# PWR_MGMT.net
KiCad netlist of a schematic drawn in Altium Designer
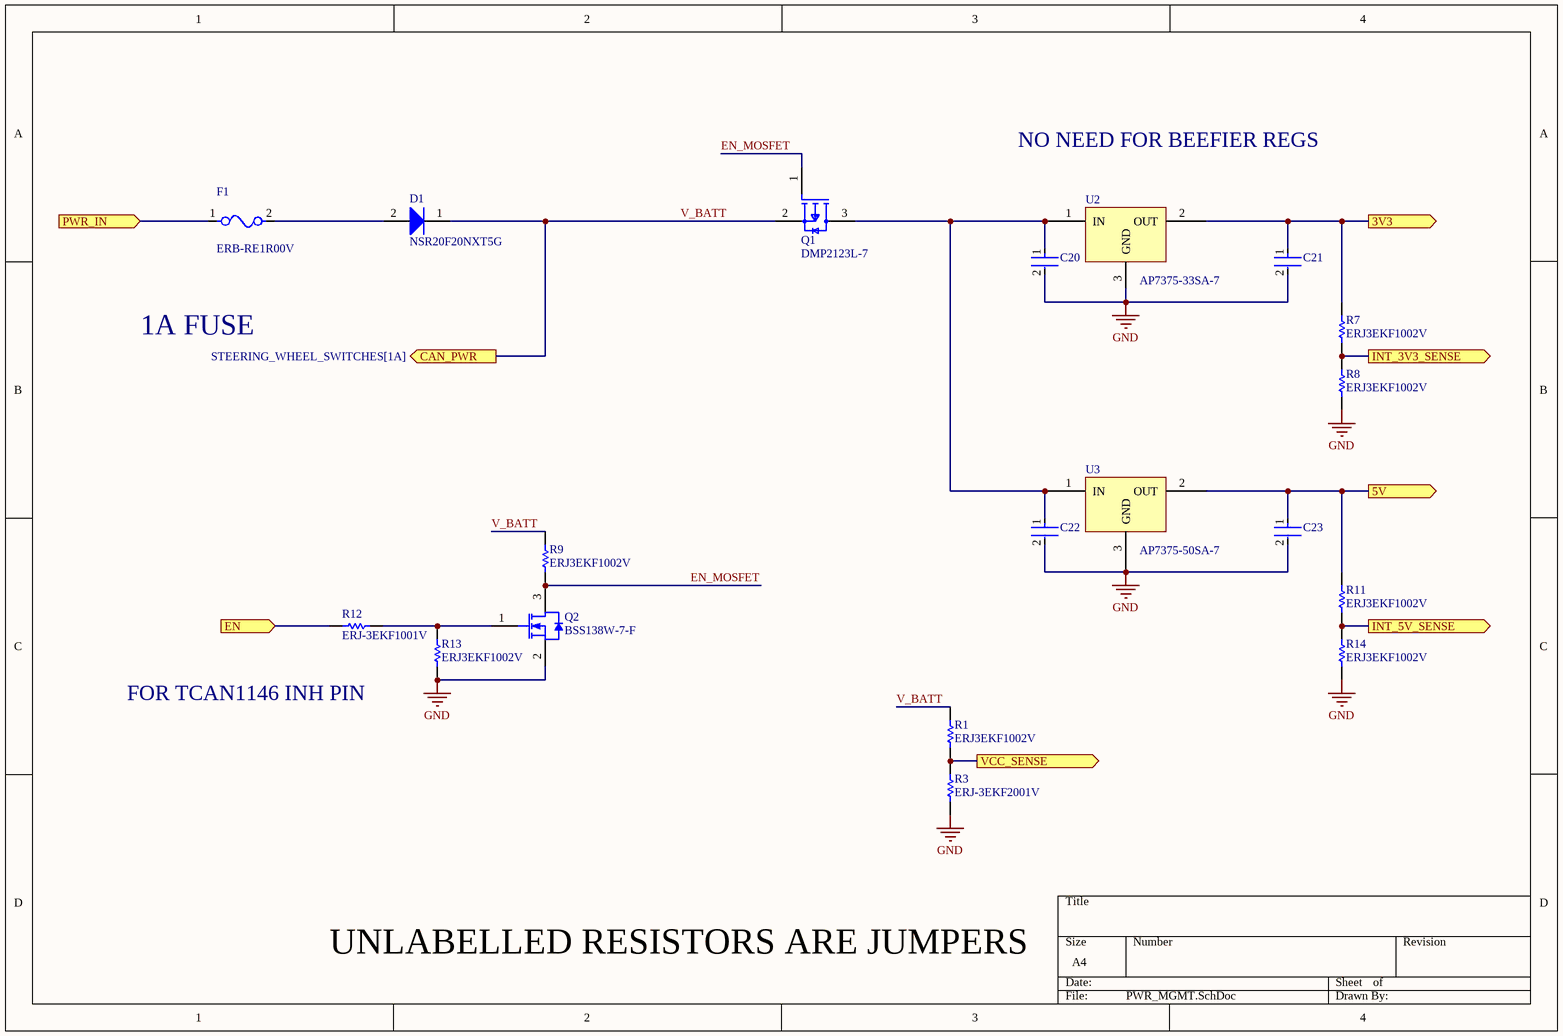
[diagram p0: PWR_MGMT.SchDoc]

(export (version "E")
  (design (tool "Eeschema 10.0.6"))
  (components
    (comp (ref "C20")
      (value "GRM188R61E106KA73D")
      (footprint "FP-GRM188-0_2-IPC_A")
      (description "Chip Multilayer Ceramic Capacitors for General Purpose, 0603, 10uF, X5R, 15%, 10%, 25V")
      (libsource (lib "Altium Content Vault") (part "11868f565c42a9108669ba33697ecf6"))
    )
    (comp (ref "C21")
      (value "GRM188R61E106KA73D")
      (footprint "FP-GRM188-0_2-IPC_A")
      (description "Chip Multilayer Ceramic Capacitors for General Purpose, 0603, 10uF, X5R, 15%, 10%, 25V")
      (libsource (lib "Altium Content Vault") (part "11868f565c42a9108669ba33697ecf6"))
    )
    (comp (ref "C22")
      (value "GRM188R61E106KA73D")
      (footprint "FP-GRM188-0_2-IPC_A")
      (description "Chip Multilayer Ceramic Capacitors for General Purpose, 0603, 10uF, X5R, 15%, 10%, 25V")
      (libsource (lib "Altium Content Vault") (part "11868f565c42a9108669ba33697ecf6"))
    )
    (comp (ref "C23")
      (value "GRM188R61E106KA73D")
      (footprint "FP-GRM188-0_2-IPC_A")
      (description "Chip Multilayer Ceramic Capacitors for General Purpose, 0603, 10uF, X5R, 15%, 10%, 25V")
      (libsource (lib "Altium Content Vault") (part "11868f565c42a9108669ba33697ecf6"))
    )
    (comp (ref "D1")
      (value "NSR20F20NXT5G")
      (footprint "ONSC-DSN-2-512AB-01_V")
      (description "Schottky Barrier Diode, 2-Pin DSN, Pb-Free, Tape and Reel")
      (fields (field (name "MANUFACTURER") "On Semiconductor"))
      (libsource (lib "Altium Content Vault") (part "ONSC-D-K1A2-2"))
    )
    (comp (ref "F1")
      (value "ERB-RE1R00V")
      (footprint "FP-ERBRE-MFG")
      (description "ERB-RE1R00V Fuse Chip Fast Acting 1A 32V SMD Solder Pad 0603 1.6 X 0.8 X 0.54mm T/R UL/cUL")
      (libsource (lib "Altium Content Vault") (part "ERB-RE1R00V"))
    )
    (comp (ref "Q1")
      (value "DMP2123L-7")
      (footprint "FP-SOT23-MFG")
      (description "DMP2123L-7 P-Channel 20 V 72 mO Surface Mount Enhancement Mode Mosfet - SOT-23")
      (libsource (lib "Altium Content Vault") (part "8f1708a9e0ba5cb1eb487dcd8f6de00"))
    )
    (comp (ref "Q2")
      (value "BSS138W-7-F")
      (footprint "DIOD-SOT323-3_V")
      (fields (field (name "MANUFACTURER") "DiodesIncorporated"))
      (libsource (lib "Altium Content Vault") (part "NEMOS-GSD-3"))
    )
    (comp (ref "R1")
      (value "ERJ3EKF1002V")
      (footprint "RESC1609X55X30LL15T15")
      (description "Chip Resistor, 10 KOhm, +/- 1%, 0.1 W, -55 to 155 degC, 0603 (1608 Metric), RoHS, Tape and Reel")
      (fields (field (name "TOLERANCE") "1%") (field (name "MANUFACTURER") "Panasonic"))
      (libsource (lib "Altium Content Vault") (part "RES-2"))
    )
    (comp (ref "R3")
      (value "ERJ-3EKF2001V")
      (footprint "RESC1608X55X30ML15T15")
      (fields (field (name "MANUFACTURER") "Panasonic"))
      (libsource (lib "Altium Content Vault") (part "RES"))
    )
    (comp (ref "R7")
      (value "ERJ3EKF1002V")
      (footprint "RESC1609X55X30LL15T15")
      (description "Chip Resistor, 10 KOhm, +/- 1%, 0.1 W, -55 to 155 degC, 0603 (1608 Metric), RoHS, Tape and Reel")
      (fields (field (name "TOLERANCE") "1%") (field (name "MANUFACTURER") "Panasonic"))
      (libsource (lib "Altium Content Vault") (part "RES-2"))
    )
    (comp (ref "R8")
      (value "ERJ3EKF1002V")
      (footprint "RESC1609X55X30LL15T15")
      (description "Chip Resistor, 10 KOhm, +/- 1%, 0.1 W, -55 to 155 degC, 0603 (1608 Metric), RoHS, Tape and Reel")
      (fields (field (name "TOLERANCE") "1%") (field (name "MANUFACTURER") "Panasonic"))
      (libsource (lib "Altium Content Vault") (part "RES-2"))
    )
    (comp (ref "R9")
      (value "ERJ3EKF1002V")
      (footprint "RESC1609X55X30LL15T15")
      (description "Chip Resistor, 10 KOhm, +/- 1%, 0.1 W, -55 to 155 degC, 0603 (1608 Metric), RoHS, Tape and Reel")
      (fields (field (name "TOLERANCE") "1%") (field (name "MANUFACTURER") "Panasonic"))
      (libsource (lib "Altium Content Vault") (part "RES-2"))
    )
    (comp (ref "R11")
      (value "ERJ3EKF1002V")
      (footprint "RESC1609X55X30LL15T15")
      (description "Chip Resistor, 10 KOhm, +/- 1%, 0.1 W, -55 to 155 degC, 0603 (1608 Metric), RoHS, Tape and Reel")
      (fields (field (name "TOLERANCE") "1%") (field (name "MANUFACTURER") "Panasonic"))
      (libsource (lib "Altium Content Vault") (part "RES-2"))
    )
    (comp (ref "R12")
      (value "ERJ-3EKF1001V")
      (footprint "RESC1608X55X30LL15T15")
      (fields (field (name "MANUFACTURER") "Panasonic"))
      (libsource (lib "Altium Content Vault") (part "RES"))
    )
    (comp (ref "R13")
      (value "ERJ3EKF1002V")
      (footprint "RESC1609X55X30LL15T15")
      (description "Chip Resistor, 10 KOhm, +/- 1%, 0.1 W, -55 to 155 degC, 0603 (1608 Metric), RoHS, Tape and Reel")
      (fields (field (name "TOLERANCE") "1%") (field (name "MANUFACTURER") "Panasonic"))
      (libsource (lib "Altium Content Vault") (part "RES-2"))
    )
    (comp (ref "R14")
      (value "ERJ3EKF1002V")
      (footprint "RESC1609X55X30LL15T15")
      (description "Chip Resistor, 10 KOhm, +/- 1%, 0.1 W, -55 to 155 degC, 0603 (1608 Metric), RoHS, Tape and Reel")
      (fields (field (name "TOLERANCE") "1%") (field (name "MANUFACTURER") "Panasonic"))
      (libsource (lib "Altium Content Vault") (part "RES-2"))
    )
    (comp (ref "U2")
      (value "AP7375-33SA-7")
      (footprint "SOT90P285X110-3N")
      (description "LDO Regulator Pos 3.3V 0.3A 3-Pin SOT-23 T/R")
      (libsource (lib "Space Concordia") (part "AP7375-33SA-7"))
    )
    (comp (ref "U3")
      (value "AP7375-50SA-7")
      (footprint "AP7375-50SA-7-Footprint-1")
      (description "Ldo Cmos Lowcurr SOT23 T&r 3K")
      (libsource (lib "Space Concordia") (part "AP7375-50SA-7"))
    )
  )
  (nets
    (net (code "1") (name "/3V3") (class "Default")
      (node (ref "C21") (pin "1") (pinfunction "1_1") (pintype "passive"))
      (node (ref "R7") (pin "2") (pinfunction "2_2") (pintype "passive"))
      (node (ref "U2") (pin "2") (pinfunction "OUT_2") (pintype "passive"))
    )
    (net (code "2") (name "/5V") (class "Default")
      (node (ref "C23") (pin "1") (pinfunction "1_1") (pintype "passive"))
      (node (ref "R11") (pin "2") (pinfunction "2_2") (pintype "passive"))
      (node (ref "U3") (pin "2") (pinfunction "OUT_2") (pintype "passive"))
    )
    (net (code "3") (name "/EN") (class "Default")
      (node (ref "R12") (pin "2") (pinfunction "2_2") (pintype "passive"))
    )
    (net (code "4") (name "/EN_MOSFET") (class "Default")
      (node (ref "Q1") (pin "1") (pinfunction "G_1") (pintype "passive"))
      (node (ref "Q2") (pin "3") (pinfunction "D_3") (pintype "passive"))
      (node (ref "R9") (pin "1") (pinfunction "1_1") (pintype "passive"))
    )
    (net (code "5") (name "/INT_3V3_SENSE") (class "Default")
      (node (ref "R7") (pin "1") (pinfunction "1_1") (pintype "passive"))
      (node (ref "R8") (pin "2") (pinfunction "2_2") (pintype "passive"))
    )
    (net (code "6") (name "/INT_5V_SENSE") (class "Default")
      (node (ref "R11") (pin "1") (pinfunction "1_1") (pintype "passive"))
      (node (ref "R14") (pin "1") (pinfunction "1_1") (pintype "passive"))
    )
    (net (code "7") (name "/PWR_IN") (class "Default")
      (node (ref "F1") (pin "1") (pinfunction "1_1") (pintype "passive"))
    )
    (net (code "8") (name "/VCC_SENSE") (class "Default")
      (node (ref "R1") (pin "1") (pinfunction "1_1") (pintype "passive"))
      (node (ref "R3") (pin "2") (pinfunction "2_2") (pintype "passive"))
    )
    (net (code "9") (name "/V_BATT") (class "Default")
      (node (ref "D1") (pin "1") (pinfunction "K_1") (pintype "passive"))
      (node (ref "Q1") (pin "2") (pinfunction "S_2") (pintype "passive"))
      (node (ref "R1") (pin "2") (pinfunction "2_2") (pintype "passive"))
      (node (ref "R9") (pin "2") (pinfunction "2_2") (pintype "passive"))
    )
    (net (code "10") (name "GND") (class "Default")
      (node (ref "C20") (pin "2") (pinfunction "2_2") (pintype "passive"))
      (node (ref "C21") (pin "2") (pinfunction "2_2") (pintype "passive"))
      (node (ref "C22") (pin "2") (pinfunction "2_2") (pintype "passive"))
      (node (ref "C23") (pin "2") (pinfunction "2_2") (pintype "passive"))
      (node (ref "Q2") (pin "2") (pinfunction "S_2") (pintype "passive"))
      (node (ref "R13") (pin "1") (pinfunction "1_1") (pintype "passive"))
      (node (ref "R14") (pin "2") (pinfunction "2_2") (pintype "passive"))
      (node (ref "R3") (pin "1") (pinfunction "1_1") (pintype "passive"))
      (node (ref "R8") (pin "1") (pinfunction "1_1") (pintype "passive"))
      (node (ref "U2") (pin "3") (pinfunction "GND_3") (pintype "passive"))
      (node (ref "U3") (pin "3") (pinfunction "GND_3") (pintype "passive"))
    )
    (net (code "11") (name "Net-(D1-A)") (class "Default")
      (node (ref "D1") (pin "2") (pinfunction "A_2") (pintype "passive"))
      (node (ref "F1") (pin "2") (pinfunction "2_2") (pintype "passive"))
    )
    (net (code "12") (name "Net-(Q1-D)") (class "Default")
      (node (ref "C20") (pin "1") (pinfunction "1_1") (pintype "passive"))
      (node (ref "C22") (pin "1") (pinfunction "1_1") (pintype "passive"))
      (node (ref "Q1") (pin "3") (pinfunction "D_3") (pintype "passive"))
      (node (ref "U2") (pin "1") (pinfunction "IN_1") (pintype "passive"))
      (node (ref "U3") (pin "1") (pinfunction "IN_1") (pintype "passive"))
    )
    (net (code "13") (name "Net-(Q2-G)") (class "Default")
      (node (ref "Q2") (pin "1") (pinfunction "G_1") (pintype "passive"))
      (node (ref "R12") (pin "1") (pinfunction "1_1") (pintype "passive"))
      (node (ref "R13") (pin "2") (pinfunction "2_2") (pintype "passive"))
    )
  )
)
